# Sheet1.net
KiCad netlist of a schematic drawn in Altium Designer
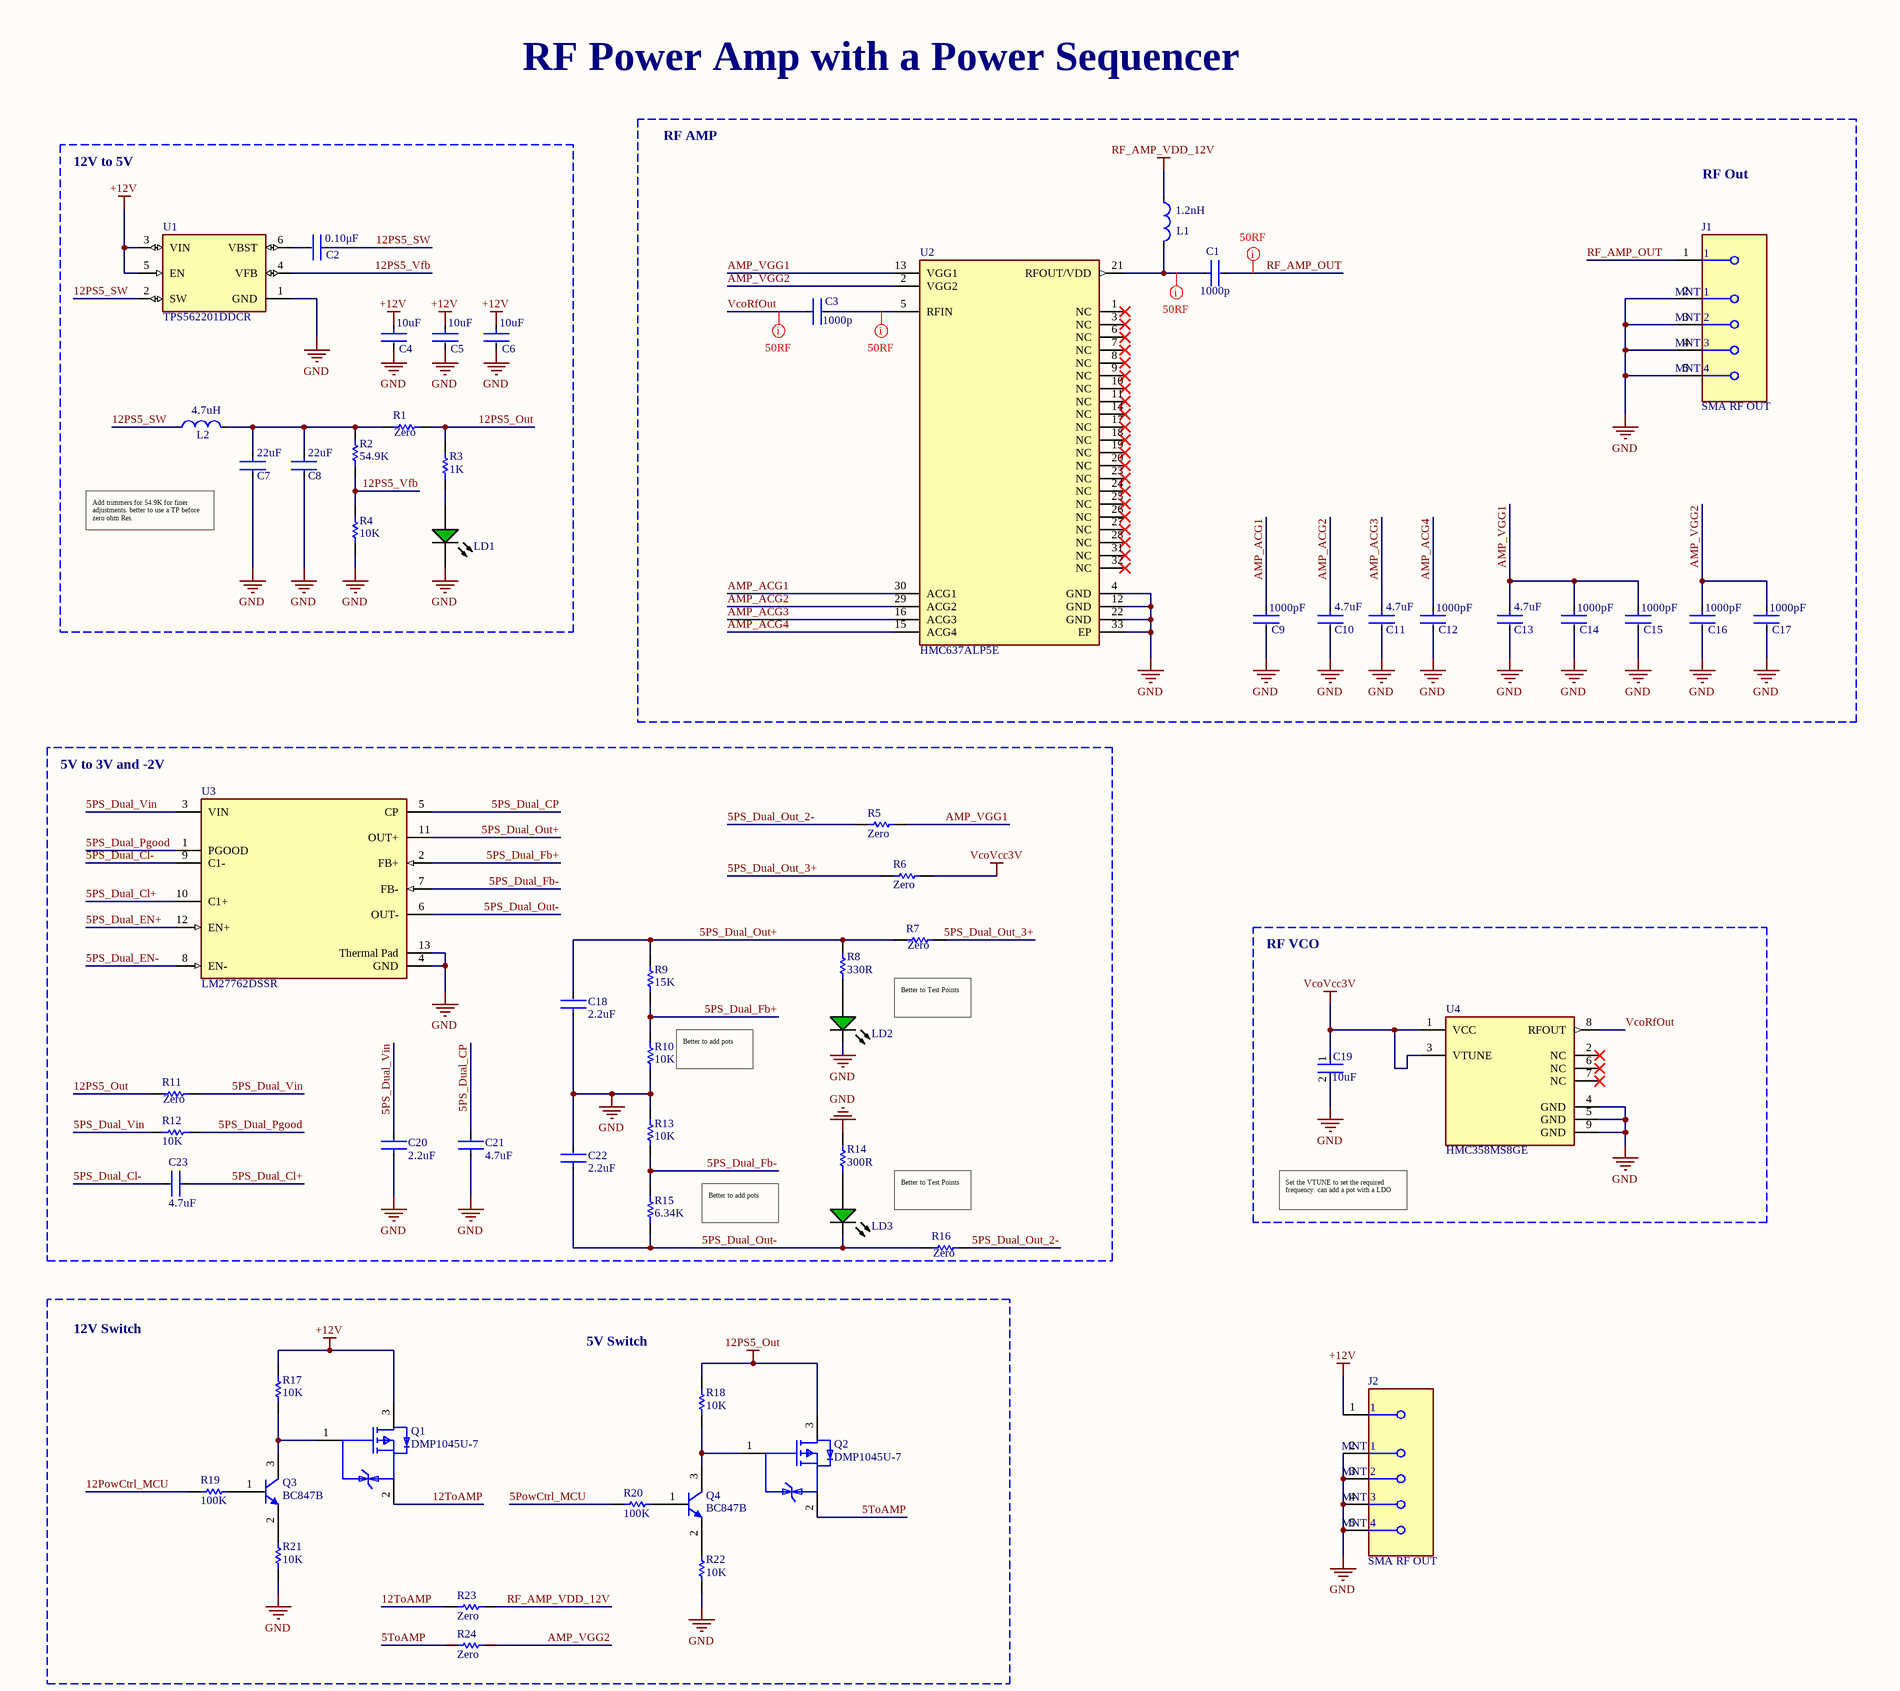
[diagram p0: Sheet1.SchDoc, top]
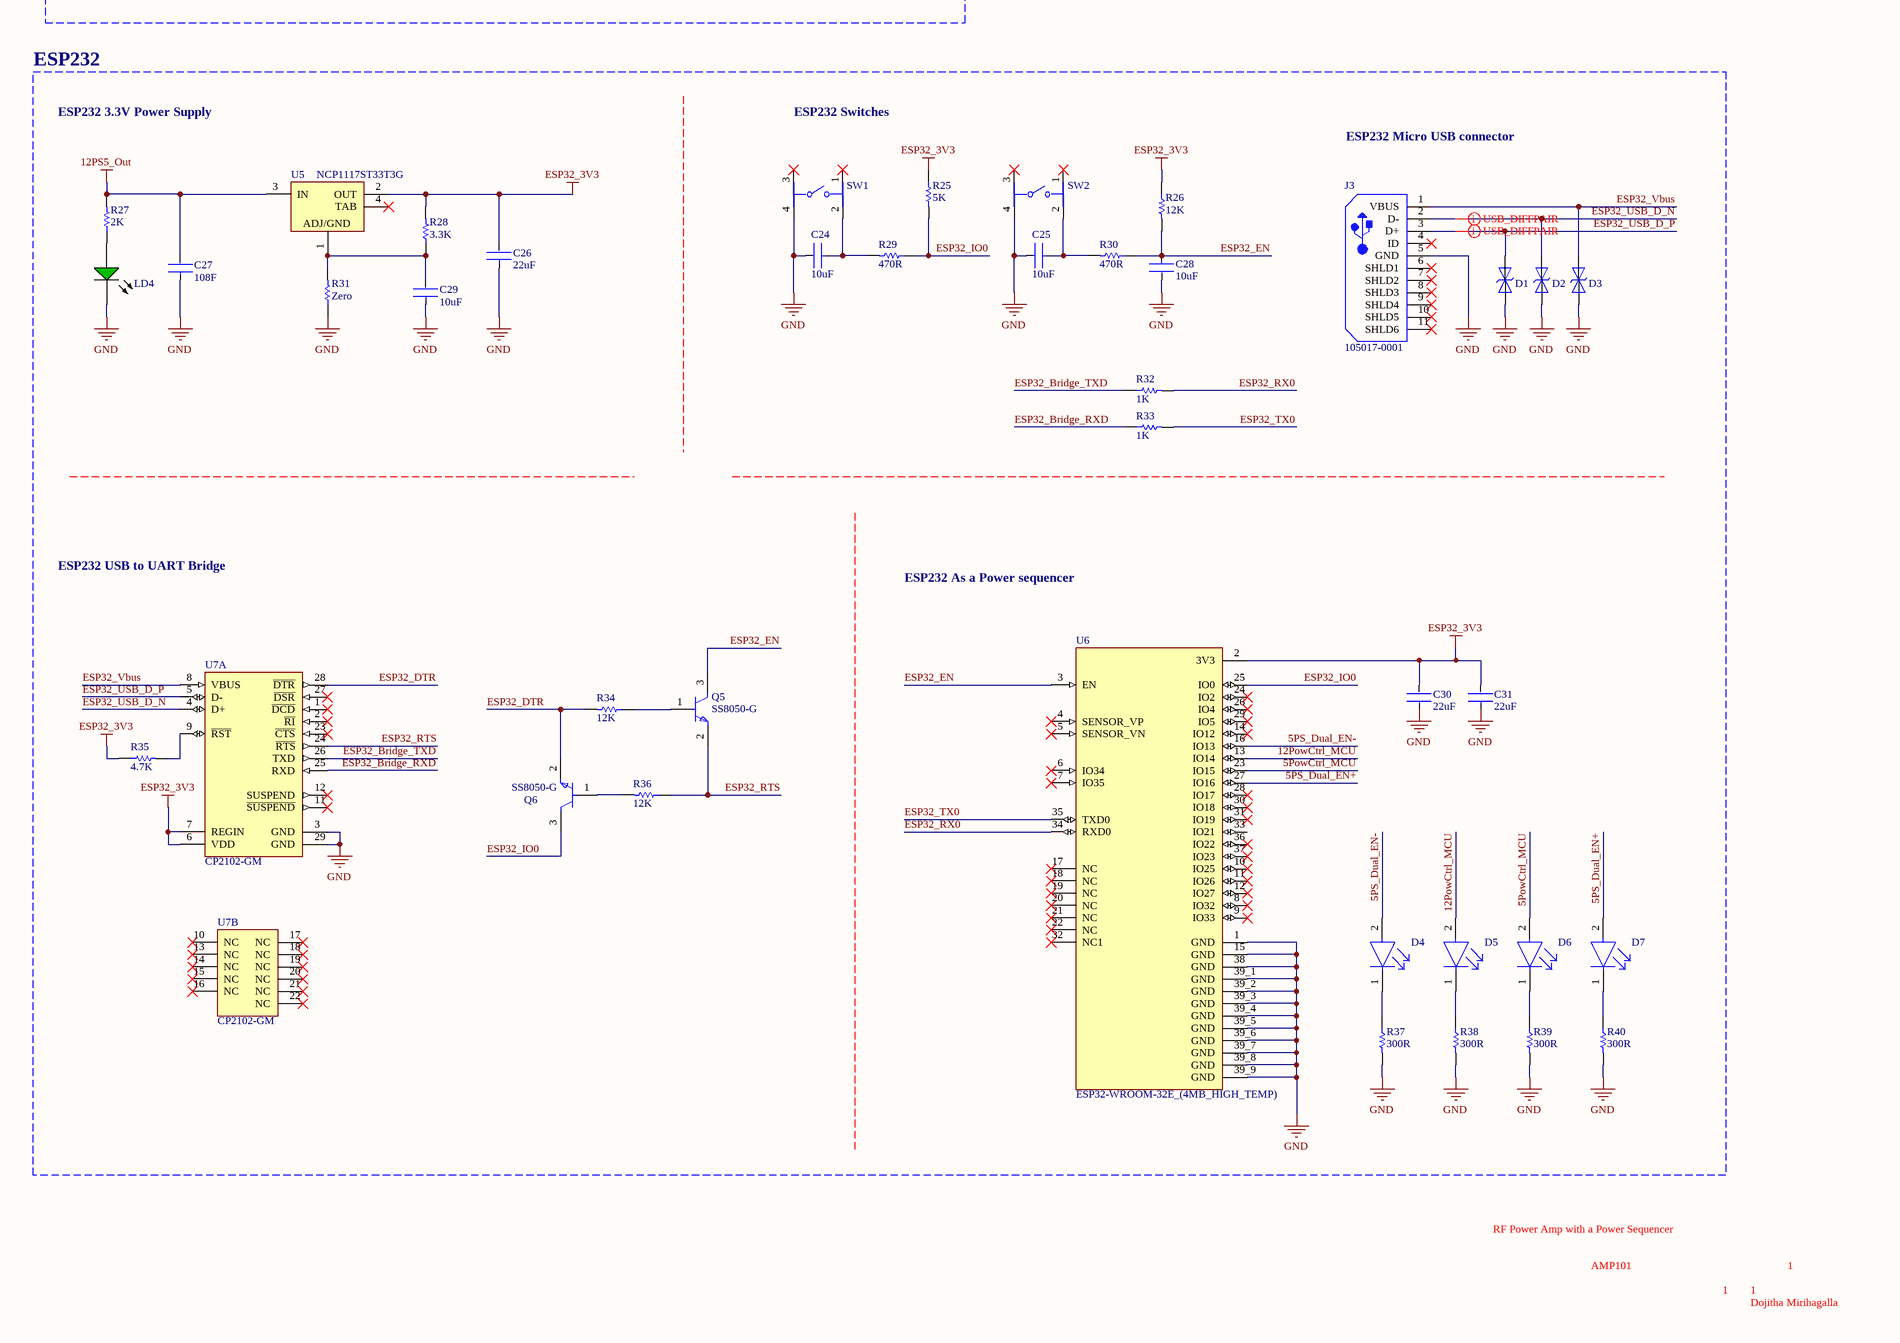
[diagram p1: Sheet1.SchDoc, bottom]

(export (version "E")
  (design (tool "Eeschema 10.0.6"))
  (components
    (comp (ref "C1")
      (value "GCM1555C1H102FA16D")
      (footprint "FP-GCM155-0_05-IPC_A")
      (description "Ceramic Capacitor for Automotive 1nF ±1% 50VDC C0G 0402 Paper T/R")
      (fields (field (name "CAPACITANCE") "1000p") (field (name "TOLERANCE") "1%"))
      (libsource (lib "Altium Content Vault") (part "02cd4be3c70576c341d710602a673aa"))
    )
    (comp (ref "C2")
      (value "GRM155R71C104KA88D")
      (footprint "FP-GRM15-MFG")
      (description "CAP CER 0.1UF 16V X7R 0402")
      (fields
        (field (name "TOLERANCE") "10%")
        (field (name "OCTOPART") "https://octopart.com/grm155r71c104ka88d-murata-196880")
        (field (name "CAPACITANCE") "0.10μF")
      )
      (libsource (lib "Altium Content Vault") (part "236180d848d6139a670b325ea6854c9"))
    )
    (comp (ref "C3")
      (value "GCM1555C1H102FA16D")
      (footprint "FP-GCM155-0_05-IPC_A")
      (description "Ceramic Capacitor for Automotive 1nF ±1% 50VDC C0G 0402 Paper T/R")
      (fields (field (name "CAPACITANCE") "1000p") (field (name "TOLERANCE") "1%"))
      (libsource (lib "Altium Content Vault") (part "02cd4be3c70576c341d710602a673aa"))
    )
    (comp (ref "C4")
      (value "GRM188R60J106ME47D")
      (footprint "FP-GRM188-0_1-e0_2_0_55-IPC_A")
      (description "Chip Multilayer Ceramic Capacitors for General Purpose, 0603, 10uF, X5R, 15%, 20%, 6.3V")
      (fields
        (field (name "CAPACITANCE") "10uF")
        (field (name "VOLTAGE") "6.3V")
        (field (name "TOLERANCE") "20%")
      )
      (libsource (lib "Altium Content Vault") (part "02cd4be3c70576c341d710602a673aa"))
    )
    (comp (ref "C5")
      (value "GRM188R60J106ME47D")
      (footprint "FP-GRM188-0_1-e0_2_0_55-IPC_A")
      (description "Chip Multilayer Ceramic Capacitors for General Purpose, 0603, 10uF, X5R, 15%, 20%, 6.3V")
      (fields
        (field (name "CAPACITANCE") "10uF")
        (field (name "VOLTAGE") "6.3V")
        (field (name "TOLERANCE") "20%")
      )
      (libsource (lib "Altium Content Vault") (part "02cd4be3c70576c341d710602a673aa"))
    )
    (comp (ref "C6")
      (value "GRM188R60J106ME47D")
      (footprint "FP-GRM188-0_1-e0_2_0_55-IPC_A")
      (description "Chip Multilayer Ceramic Capacitors for General Purpose, 0603, 10uF, X5R, 15%, 20%, 6.3V")
      (fields
        (field (name "CAPACITANCE") "10uF")
        (field (name "VOLTAGE") "6.3V")
        (field (name "TOLERANCE") "20%")
      )
      (libsource (lib "Altium Content Vault") (part "02cd4be3c70576c341d710602a673aa"))
    )
    (comp (ref "C7")
      (value "GRM21BR60J226ME39L")
      (footprint "FP-GRM21B-0_15-MFG")
      (description "Chip Multilayer Ceramic Capacitors for General Purpose, 0805, 22uF, X5R, 15%, 20%, 6.3V")
      (fields
        (field (name "VOLTAGE") "6.3V")
        (field (name "TOLERANCE") "20%")
        (field (name "CAPACITANCE") "22uF")
      )
      (libsource (lib "Altium Content Vault") (part "b4654b650e69147ec39a6b967a45e02"))
    )
    (comp (ref "C8")
      (value "GRM21BR60J226ME39L")
      (footprint "FP-GRM21B-0_15-MFG")
      (description "Chip Multilayer Ceramic Capacitors for General Purpose, 0805, 22uF, X5R, 15%, 20%, 6.3V")
      (fields
        (field (name "VOLTAGE") "6.3V")
        (field (name "TOLERANCE") "20%")
        (field (name "CAPACITANCE") "22uF")
      )
      (libsource (lib "Altium Content Vault") (part "b4654b650e69147ec39a6b967a45e02"))
    )
    (comp (ref "C9")
      (value "06035C102KAT2A")
      (footprint "FP-0603-L_1_6_0_15-W_0_81-IPC_A")
      (description "General Purpose Ceramic Capacitor, 0603, 1nF, 10%, X7R, 15%, 50V")
      (fields
        (field (name "CAPACITANCE") "1000pF")
        (field (name "VOLTAGE") "50V")
        (field (name "TOLERANCE") "10%")
      )
      (libsource (lib "Altium Content Vault") (part "02cd4be3c70576c341d710602a673aa"))
    )
    (comp (ref "C10")
      (value "CL05A475MP5NRNC")
      (footprint "FP-CL282-IPC_C")
      (description "Cap Ceramic 4.7uF 10V X5R ±20% SMD 0402 +85°C Paper T/R")
      (fields (field (name "CAPACITANCE") "4.7uF") (field (name "TOLERANCE") "20%"))
      (libsource (lib "Altium Content Vault") (part "b4654b650e69147ec39a6b967a45e02"))
    )
    (comp (ref "C11")
      (value "CL05A475MP5NRNC")
      (footprint "FP-CL282-IPC_C")
      (description "Cap Ceramic 4.7uF 10V X5R ±20% SMD 0402 +85°C Paper T/R")
      (fields (field (name "CAPACITANCE") "4.7uF") (field (name "TOLERANCE") "20%"))
      (libsource (lib "Altium Content Vault") (part "b4654b650e69147ec39a6b967a45e02"))
    )
    (comp (ref "C12")
      (value "06035C102KAT2A")
      (footprint "FP-0603-L_1_6_0_15-W_0_81-IPC_A")
      (description "General Purpose Ceramic Capacitor, 0603, 1nF, 10%, X7R, 15%, 50V")
      (fields
        (field (name "CAPACITANCE") "1000pF")
        (field (name "VOLTAGE") "50V")
        (field (name "TOLERANCE") "10%")
      )
      (libsource (lib "Altium Content Vault") (part "02cd4be3c70576c341d710602a673aa"))
    )
    (comp (ref "C13")
      (value "CL05A475MP5NRNC")
      (footprint "FP-CL282-IPC_C")
      (description "Cap Ceramic 4.7uF 10V X5R ±20% SMD 0402 +85°C Paper T/R")
      (fields (field (name "CAPACITANCE") "4.7uF") (field (name "TOLERANCE") "20%"))
      (libsource (lib "Altium Content Vault") (part "b4654b650e69147ec39a6b967a45e02"))
    )
    (comp (ref "C14")
      (value "06035C102KAT2A")
      (footprint "FP-0603-L_1_6_0_15-W_0_81-IPC_A")
      (description "General Purpose Ceramic Capacitor, 0603, 1nF, 10%, X7R, 15%, 50V")
      (fields
        (field (name "CAPACITANCE") "1000pF")
        (field (name "VOLTAGE") "50V")
        (field (name "TOLERANCE") "10%")
      )
      (libsource (lib "Altium Content Vault") (part "02cd4be3c70576c341d710602a673aa"))
    )
    (comp (ref "C15")
      (value "06035C102KAT2A")
      (footprint "FP-0603-L_1_6_0_15-W_0_81-IPC_A")
      (description "General Purpose Ceramic Capacitor, 0603, 1nF, 10%, X7R, 15%, 50V")
      (fields
        (field (name "CAPACITANCE") "1000pF")
        (field (name "VOLTAGE") "50V")
        (field (name "TOLERANCE") "10%")
      )
      (libsource (lib "Altium Content Vault") (part "02cd4be3c70576c341d710602a673aa"))
    )
    (comp (ref "C16")
      (value "06035C102KAT2A")
      (footprint "FP-0603-L_1_6_0_15-W_0_81-IPC_A")
      (description "General Purpose Ceramic Capacitor, 0603, 1nF, 10%, X7R, 15%, 50V")
      (fields
        (field (name "CAPACITANCE") "1000pF")
        (field (name "VOLTAGE") "50V")
        (field (name "TOLERANCE") "10%")
      )
      (libsource (lib "Altium Content Vault") (part "02cd4be3c70576c341d710602a673aa"))
    )
    (comp (ref "C17")
      (value "06035C102KAT2A")
      (footprint "FP-0603-L_1_6_0_15-W_0_81-IPC_A")
      (description "General Purpose Ceramic Capacitor, 0603, 1nF, 10%, X7R, 15%, 50V")
      (fields
        (field (name "CAPACITANCE") "1000pF")
        (field (name "VOLTAGE") "50V")
        (field (name "TOLERANCE") "10%")
      )
      (libsource (lib "Altium Content Vault") (part "02cd4be3c70576c341d710602a673aa"))
    )
    (comp (ref "C18")
      (value "CL05A475MP5NRNC")
      (footprint "FP-CL282-IPC_C")
      (description "Cap Ceramic 4.7uF 10V X5R ±20% SMD 0402 +85°C Paper T/R")
      (fields (field (name "CAPACITANCE") "2.2uF") (field (name "TOLERANCE") "20%"))
      (libsource (lib "Altium Content Vault") (part "b4654b650e69147ec39a6b967a45e02"))
    )
    (comp (ref "C19")
      (value "GRJ155R60J106ME11D")
      (footprint "FP-GRJ155-0_2-MFG")
      (description "CAP CER 10UF 6.3V X5R 0402")
      (fields (field (name "CAPACITANCE") "10uF") (field (name "TOLERANCE") "20%"))
      (libsource (lib "Altium Content Vault") (part "11868f565c42a9108669ba33697ecf6"))
    )
    (comp (ref "C20")
      (value "CL05A475MP5NRNC")
      (footprint "FP-CL282-IPC_C")
      (description "Cap Ceramic 4.7uF 10V X5R ±20% SMD 0402 +85°C Paper T/R")
      (fields (field (name "CAPACITANCE") "2.2uF") (field (name "TOLERANCE") "20%"))
      (libsource (lib "Altium Content Vault") (part "b4654b650e69147ec39a6b967a45e02"))
    )
    (comp (ref "C21")
      (value "CL05A475MP5NRNC")
      (footprint "FP-CL282-IPC_C")
      (description "Cap Ceramic 4.7uF 10V X5R ±20% SMD 0402 +85°C Paper T/R")
      (fields (field (name "CAPACITANCE") "4.7uF") (field (name "TOLERANCE") "20%"))
      (libsource (lib "Altium Content Vault") (part "b4654b650e69147ec39a6b967a45e02"))
    )
    (comp (ref "C22")
      (value "CL05A475MP5NRNC")
      (footprint "FP-CL282-IPC_C")
      (description "Cap Ceramic 4.7uF 10V X5R ±20% SMD 0402 +85°C Paper T/R")
      (fields (field (name "CAPACITANCE") "2.2uF") (field (name "TOLERANCE") "20%"))
      (libsource (lib "Altium Content Vault") (part "b4654b650e69147ec39a6b967a45e02"))
    )
    (comp (ref "C23")
      (value "CL05A475MP5NRNC")
      (footprint "FP-CL282-IPC_C")
      (description "Cap Ceramic 4.7uF 10V X5R ±20% SMD 0402 +85°C Paper T/R")
      (fields (field (name "CAPACITANCE") "4.7uF") (field (name "TOLERANCE") "20%"))
      (libsource (lib "Altium Content Vault") (part "b4654b650e69147ec39a6b967a45e02"))
    )
    (comp (ref "C24")
      (value "CL05A475MP5NRNC")
      (footprint "FP-CL282-IPC_C")
      (description "Cap Ceramic 4.7uF 10V X5R ±20% SMD 0402 +85°C Paper T/R")
      (fields (field (name "CAPACITANCE") "10uF") (field (name "TOLERANCE") "20%"))
      (libsource (lib "Altium Content Vault") (part "b4654b650e69147ec39a6b967a45e02"))
    )
    (comp (ref "C25")
      (value "CL05A475MP5NRNC")
      (footprint "FP-CL282-IPC_C")
      (description "Cap Ceramic 4.7uF 10V X5R ±20% SMD 0402 +85°C Paper T/R")
      (fields (field (name "CAPACITANCE") "10uF") (field (name "TOLERANCE") "20%"))
      (libsource (lib "Altium Content Vault") (part "b4654b650e69147ec39a6b967a45e02"))
    )
    (comp (ref "C26")
      (value "CL05A475MP5NRNC")
      (footprint "FP-CL282-IPC_C")
      (description "Cap Ceramic 4.7uF 10V X5R ±20% SMD 0402 +85°C Paper T/R")
      (fields (field (name "CAPACITANCE") "22uF") (field (name "TOLERANCE") "20%"))
      (libsource (lib "Altium Content Vault") (part "b4654b650e69147ec39a6b967a45e02"))
    )
    (comp (ref "C27")
      (value "CL05A475MP5NRNC")
      (footprint "FP-CL282-IPC_C")
      (description "Cap Ceramic 4.7uF 10V X5R ±20% SMD 0402 +85°C Paper T/R")
      (fields (field (name "CAPACITANCE") "108F") (field (name "TOLERANCE") "20%"))
      (libsource (lib "Altium Content Vault") (part "b4654b650e69147ec39a6b967a45e02"))
    )
    (comp (ref "C28")
      (value "CL05A475MP5NRNC")
      (footprint "FP-CL282-IPC_C")
      (description "Cap Ceramic 4.7uF 10V X5R ±20% SMD 0402 +85°C Paper T/R")
      (fields (field (name "CAPACITANCE") "10uF") (field (name "TOLERANCE") "20%"))
      (libsource (lib "Altium Content Vault") (part "b4654b650e69147ec39a6b967a45e02"))
    )
    (comp (ref "C29")
      (value "CL05A475MP5NRNC")
      (footprint "FP-CL282-IPC_C")
      (description "Cap Ceramic 4.7uF 10V X5R ±20% SMD 0402 +85°C Paper T/R")
      (fields (field (name "CAPACITANCE") "10uF") (field (name "TOLERANCE") "20%"))
      (libsource (lib "Altium Content Vault") (part "b4654b650e69147ec39a6b967a45e02"))
    )
    (comp (ref "C30")
      (value "CL05A475MP5NRNC")
      (footprint "FP-CL282-IPC_C")
      (description "Cap Ceramic 4.7uF 10V X5R ±20% SMD 0402 +85°C Paper T/R")
      (fields (field (name "CAPACITANCE") "22uF") (field (name "TOLERANCE") "20%"))
      (libsource (lib "Altium Content Vault") (part "b4654b650e69147ec39a6b967a45e02"))
    )
    (comp (ref "C31")
      (value "CL05A475MP5NRNC")
      (footprint "FP-CL282-IPC_C")
      (description "Cap Ceramic 4.7uF 10V X5R ±20% SMD 0402 +85°C Paper T/R")
      (fields (field (name "CAPACITANCE") "22uF") (field (name "TOLERANCE") "20%"))
      (libsource (lib "Altium Content Vault") (part "b4654b650e69147ec39a6b967a45e02"))
    )
    (comp (ref "D1")
      (value "SMF16A")
      (footprint "SODFL3718X102N")
      (description "200W, 18.8V, 5%, Unidirectional, TVS")
      (fields (field (name "MF") "Taiwan Semiconductor"))
      (libsource (lib "Schlib1") (part "SMF16A"))
    )
    (comp (ref "D2")
      (value "SMF16A")
      (footprint "SODFL3718X102N")
      (description "200W, 18.8V, 5%, Unidirectional, TVS")
      (fields (field (name "MF") "Taiwan Semiconductor"))
      (libsource (lib "Schlib1") (part "SMF16A"))
    )
    (comp (ref "D3")
      (value "SMF16A")
      (footprint "SODFL3718X102N")
      (description "200W, 18.8V, 5%, Unidirectional, TVS")
      (fields (field (name "MF") "Taiwan Semiconductor"))
      (libsource (lib "Schlib1") (part "SMF16A"))
    )
    (comp (ref "D4")
      (value "LTST-C191TBKT")
      (footprint "FP-LTST-C191TBKT-MFG")
      (description "LED BLUE CLEAR CHIP SMD")
      (libsource (lib "Altium Content Vault") (part "8706943c75ba83719d021d2fdc84c58"))
    )
    (comp (ref "D5")
      (value "LTST-C191TBKT")
      (footprint "FP-LTST-C191TBKT-MFG")
      (description "LED BLUE CLEAR CHIP SMD")
      (libsource (lib "Altium Content Vault") (part "8706943c75ba83719d021d2fdc84c58"))
    )
    (comp (ref "D6")
      (value "LTST-C191TBKT")
      (footprint "FP-LTST-C191TBKT-MFG")
      (description "LED BLUE CLEAR CHIP SMD")
      (libsource (lib "Altium Content Vault") (part "8706943c75ba83719d021d2fdc84c58"))
    )
    (comp (ref "D7")
      (value "LTST-C191TBKT")
      (footprint "FP-LTST-C191TBKT-MFG")
      (description "LED BLUE CLEAR CHIP SMD")
      (libsource (lib "Altium Content Vault") (part "8706943c75ba83719d021d2fdc84c58"))
    )
    (comp (ref "J1")
      (value "SMA RF OUT")
      (footprint "FP-SMA-J-P-H-ST-EM1-MFG")
      (description "CONN SMA JACK STR 50OHM EDGE MNT")
      (libsource (lib "Altium Content Vault") (part "c65b8a639cdaef1819ea20b5466f8fa"))
    )
    (comp (ref "J2")
      (value "SMA RF OUT")
      (footprint "FP-SMA-J-P-H-ST-EM1-MFG")
      (description "CONN SMA JACK STR 50OHM EDGE MNT")
      (libsource (lib "Altium Content Vault") (part "c65b8a639cdaef1819ea20b5466f8fa"))
    )
    (comp (ref "J3")
      (value "105017-0001")
      (footprint "USB-MICRO-B_V")
      (fields (field (name "MANUFACTURER") "Molex"))
      (libsource (lib "Altium Content Vault") (part "USB-5-6SHLD"))
    )
    (comp (ref "L1")
      (value "LQP03HQ1N2B02D")
      (footprint "FP-LQP03HQ_02-MFG")
      (description "Film type RF Inductor 1.2nH ±0.1nH 1100mA 0.04Ω 0201 (0603)")
      (fields (field (name "INDUCTANCE") "1.2nH"))
      (libsource (lib "Altium Content Vault") (part "725321dda6339637d4d059423bc1c3c"))
    )
    (comp (ref "L2")
      (value "NR6028T4R7M")
      (footprint "FP-NR6028-MFG")
      (description "SMD Power Inductors 4.7uH ±20% 2.7A 40.3mΩ")
      (fields (field (name "INDUCTANCE") "4.7uH") (field (name "TOLERANCE") "20%"))
      (libsource (lib "Altium Content Vault") (part "725321dda6339637d4d059423bc1c3c"))
    )
    (comp (ref "LD1")
      (value "HSMG-C170")
      (footprint "AVAG-HSMX-C170_V")
      (description "Chip LED, Green, 2.2 V, -40 to 85 degC, 2-Pin SMD, Pb-Free, Tape and Reel")
      (fields (field (name "MANUFACTURER") "Avago"))
      (libsource (lib "Altium Content Vault") (part "LED_GREEN_A1K2-2"))
    )
    (comp (ref "LD2")
      (value "HSMG-C170")
      (footprint "AVAG-HSMX-C170_V")
      (description "Chip LED, Green, 2.2 V, -40 to 85 degC, 2-Pin SMD, Pb-Free, Tape and Reel")
      (fields (field (name "MANUFACTURER") "Avago"))
      (libsource (lib "Altium Content Vault") (part "LED_GREEN_A1K2-2"))
    )
    (comp (ref "LD3")
      (value "HSMG-C170")
      (footprint "AVAG-HSMX-C170_V")
      (description "Chip LED, Green, 2.2 V, -40 to 85 degC, 2-Pin SMD, Pb-Free, Tape and Reel")
      (fields (field (name "MANUFACTURER") "Avago"))
      (libsource (lib "Altium Content Vault") (part "LED_GREEN_A1K2-2"))
    )
    (comp (ref "LD4")
      (value "HSMG-C170")
      (footprint "AVAG-HSMX-C170_V")
      (description "Chip LED, Green, 2.2 V, -40 to 85 degC, 2-Pin SMD, Pb-Free, Tape and Reel")
      (fields (field (name "MANUFACTURER") "Avago"))
      (libsource (lib "Altium Content Vault") (part "LED_GREEN_A1K2-2"))
    )
    (comp (ref "Q1")
      (value "DMP1045U-7")
      (footprint "FP-SOT23-MFG")
      (description "MOSFET P-CH 12V 4A SOT23")
      (fields
        (field (name "MANUFACTURER") "Diodes Inc.")
        (field (name "OCTOPART") "https://octopart.com/dmp1045u-7-diodes+inc.-20474459")
      )
      (libsource (lib "Altium Content Vault") (part "16f57cea3a39b7f0ecfb5a0737525d1"))
    )
    (comp (ref "Q2")
      (value "DMP1045U-7")
      (footprint "FP-SOT23-MFG")
      (description "MOSFET P-CH 12V 4A SOT23")
      (fields
        (field (name "MANUFACTURER") "Diodes Inc.")
        (field (name "OCTOPART") "https://octopart.com/dmp1045u-7-diodes+inc.-20474459")
      )
      (libsource (lib "Altium Content Vault") (part "16f57cea3a39b7f0ecfb5a0737525d1"))
    )
    (comp (ref "Q3")
      (value "BC847B")
      (footprint "INF-SOT23_M")
      (description "NPN Silicon AF Transistor, 45 V VCEO, 100 mA IC, SOT23, Reel, Green")
      (fields (field (name "MANUFACTURER") "Infineon"))
      (libsource (lib "Altium Content Vault") (part "INF-BJTNPN-BEC-3"))
    )
    (comp (ref "Q4")
      (value "BC847B")
      (footprint "INF-SOT23_M")
      (description "NPN Silicon AF Transistor, 45 V VCEO, 100 mA IC, SOT23, Reel, Green")
      (fields (field (name "MANUFACTURER") "Infineon"))
      (libsource (lib "Altium Content Vault") (part "INF-BJTNPN-BEC-3"))
    )
    (comp (ref "Q5")
      (value "SS8050-G")
      (footprint "FP-SS8050-G-MFG")
      (description "NPN TRANSISTOR 1.5A 40V SOT-23 R")
      (libsource (lib "Altium Content Vault") (part "2a1388f82443b098dcd57d24ac7632d"))
    )
    (comp (ref "Q6")
      (value "SS8050-G")
      (footprint "FP-SS8050-G-MFG")
      (description "NPN TRANSISTOR 1.5A 40V SOT-23 R")
      (libsource (lib "Altium Content Vault") (part "2a1388f82443b098dcd57d24ac7632d"))
    )
    (comp (ref "R1")
      (value "CRCW060354K9FKEA")
      (footprint "RESC1609X50X30LL10T20")
      (fields (field (name "MANUFACTURER") "Vishay Dale") (field (name "RESISTANCE") "Zero"))
      (libsource (lib "Altium Content Vault") (part "RES"))
    )
    (comp (ref "R2")
      (value "CRCW060354K9FKEA")
      (footprint "RESC1609X50X30LL10T20")
      (fields (field (name "MANUFACTURER") "Vishay Dale") (field (name "RESISTANCE") "54.9K"))
      (libsource (lib "Altium Content Vault") (part "RES"))
    )
    (comp (ref "R3")
      (value "CRCW060354K9FKEA")
      (footprint "RESC1609X50X30LL10T20")
      (fields (field (name "MANUFACTURER") "Vishay Dale") (field (name "RESISTANCE") "1K"))
      (libsource (lib "Altium Content Vault") (part "RES"))
    )
    (comp (ref "R4")
      (value "CRCW060354K9FKEA")
      (footprint "RESC1609X50X30LL10T20")
      (fields (field (name "MANUFACTURER") "Vishay Dale") (field (name "RESISTANCE") "10K"))
      (libsource (lib "Altium Content Vault") (part "RES"))
    )
    (comp (ref "R5")
      (value "CRCW060354K9FKEA")
      (footprint "RESC1609X50X30LL10T20")
      (fields (field (name "MANUFACTURER") "Vishay Dale") (field (name "RESISTANCE") "Zero"))
      (libsource (lib "Altium Content Vault") (part "RES"))
    )
    (comp (ref "R6")
      (value "CRCW060354K9FKEA")
      (footprint "RESC1609X50X30LL10T20")
      (fields (field (name "MANUFACTURER") "Vishay Dale") (field (name "RESISTANCE") "Zero"))
      (libsource (lib "Altium Content Vault") (part "RES"))
    )
    (comp (ref "R7")
      (value "CRCW060354K9FKEA")
      (footprint "RESC1609X50X30LL10T20")
      (fields (field (name "MANUFACTURER") "Vishay Dale") (field (name "RESISTANCE") "Zero"))
      (libsource (lib "Altium Content Vault") (part "RES"))
    )
    (comp (ref "R8")
      (value "CRCW060354K9FKEA")
      (footprint "RESC1609X50X30LL10T20")
      (fields (field (name "MANUFACTURER") "Vishay Dale") (field (name "RESISTANCE") "330R"))
      (libsource (lib "Altium Content Vault") (part "RES"))
    )
    (comp (ref "R9")
      (value "CRCW060354K9FKEA")
      (footprint "RESC1609X50X30LL10T20")
      (fields (field (name "MANUFACTURER") "Vishay Dale") (field (name "RESISTANCE") "15K"))
      (libsource (lib "Altium Content Vault") (part "RES"))
    )
    (comp (ref "R10")
      (value "CRCW060354K9FKEA")
      (footprint "RESC1609X50X30LL10T20")
      (fields (field (name "MANUFACTURER") "Vishay Dale") (field (name "RESISTANCE") "10K"))
      (libsource (lib "Altium Content Vault") (part "RES"))
    )
    (comp (ref "R11")
      (value "CRCW060354K9FKEA")
      (footprint "RESC1609X50X30LL10T20")
      (fields (field (name "MANUFACTURER") "Vishay Dale") (field (name "RESISTANCE") "Zero"))
      (libsource (lib "Altium Content Vault") (part "RES"))
    )
    (comp (ref "R12")
      (value "CRCW060354K9FKEA")
      (footprint "RESC1609X50X30LL10T20")
      (fields (field (name "MANUFACTURER") "Vishay Dale") (field (name "RESISTANCE") "10K"))
      (libsource (lib "Altium Content Vault") (part "RES"))
    )
    (comp (ref "R13")
      (value "CRCW060354K9FKEA")
      (footprint "RESC1609X50X30LL10T20")
      (fields (field (name "MANUFACTURER") "Vishay Dale") (field (name "RESISTANCE") "10K"))
      (libsource (lib "Altium Content Vault") (part "RES"))
    )
    (comp (ref "R14")
      (value "CRCW060354K9FKEA")
      (footprint "RESC1609X50X30LL10T20")
      (fields (field (name "MANUFACTURER") "Vishay Dale") (field (name "RESISTANCE") "300R"))
      (libsource (lib "Altium Content Vault") (part "RES"))
    )
    (comp (ref "R15")
      (value "CRCW060354K9FKEA")
      (footprint "RESC1609X50X30LL10T20")
      (fields (field (name "MANUFACTURER") "Vishay Dale") (field (name "RESISTANCE") "6.34K"))
      (libsource (lib "Altium Content Vault") (part "RES"))
    )
    (comp (ref "R16")
      (value "CRCW060354K9FKEA")
      (footprint "RESC1609X50X30LL10T20")
      (fields (field (name "MANUFACTURER") "Vishay Dale") (field (name "RESISTANCE") "Zero"))
      (libsource (lib "Altium Content Vault") (part "RES"))
    )
    (comp (ref "R17")
      (value "CRCW060354K9FKEA")
      (footprint "RESC1609X50X30LL10T20")
      (fields (field (name "MANUFACTURER") "Vishay Dale") (field (name "RESISTANCE") "10K"))
      (libsource (lib "Altium Content Vault") (part "RES"))
    )
    (comp (ref "R18")
      (value "CRCW060354K9FKEA")
      (footprint "RESC1609X50X30LL10T20")
      (fields (field (name "MANUFACTURER") "Vishay Dale") (field (name "RESISTANCE") "10K"))
      (libsource (lib "Altium Content Vault") (part "RES"))
    )
    (comp (ref "R19")
      (value "CRCW060354K9FKEA")
      (footprint "RESC1609X50X30LL10T20")
      (fields (field (name "MANUFACTURER") "Vishay Dale") (field (name "RESISTANCE") "100K"))
      (libsource (lib "Altium Content Vault") (part "RES"))
    )
    (comp (ref "R20")
      (value "CRCW060354K9FKEA")
      (footprint "RESC1609X50X30LL10T20")
      (fields (field (name "MANUFACTURER") "Vishay Dale") (field (name "RESISTANCE") "100K"))
      (libsource (lib "Altium Content Vault") (part "RES"))
    )
    (comp (ref "R21")
      (value "CRCW060354K9FKEA")
      (footprint "RESC1609X50X30LL10T20")
      (fields (field (name "MANUFACTURER") "Vishay Dale") (field (name "RESISTANCE") "10K"))
      (libsource (lib "Altium Content Vault") (part "RES"))
    )
    (comp (ref "R22")
      (value "CRCW060354K9FKEA")
      (footprint "RESC1609X50X30LL10T20")
      (fields (field (name "MANUFACTURER") "Vishay Dale") (field (name "RESISTANCE") "10K"))
      (libsource (lib "Altium Content Vault") (part "RES"))
    )
    (comp (ref "R23")
      (value "CRCW060354K9FKEA")
      (footprint "RESC1609X50X30LL10T20")
      (fields (field (name "MANUFACTURER") "Vishay Dale") (field (name "RESISTANCE") "Zero"))
      (libsource (lib "Altium Content Vault") (part "RES"))
    )
    (comp (ref "R24")
      (value "CRCW060354K9FKEA")
      (footprint "RESC1609X50X30LL10T20")
      (fields (field (name "MANUFACTURER") "Vishay Dale") (field (name "RESISTANCE") "Zero"))
      (libsource (lib "Altium Content Vault") (part "RES"))
    )
    (comp (ref "R25")
      (value "CRCW060354K9FKEA")
      (footprint "RESC1609X50X30LL10T20")
      (fields (field (name "MANUFACTURER") "Vishay Dale") (field (name "RESISTANCE") "5K"))
      (libsource (lib "Altium Content Vault") (part "RES"))
    )
    (comp (ref "R26")
      (value "CRCW060354K9FKEA")
      (footprint "RESC1609X50X30LL10T20")
      (fields (field (name "MANUFACTURER") "Vishay Dale") (field (name "RESISTANCE") "12K"))
      (libsource (lib "Altium Content Vault") (part "RES"))
    )
    (comp (ref "R27")
      (value "CRCW060354K9FKEA")
      (footprint "RESC1609X50X30LL10T20")
      (fields (field (name "MANUFACTURER") "Vishay Dale") (field (name "RESISTANCE") "2K"))
      (libsource (lib "Altium Content Vault") (part "RES"))
    )
    (comp (ref "R28")
      (value "CRCW060354K9FKEA")
      (footprint "RESC1609X50X30LL10T20")
      (fields (field (name "MANUFACTURER") "Vishay Dale") (field (name "RESISTANCE") "3.3K"))
      (libsource (lib "Altium Content Vault") (part "RES"))
    )
    (comp (ref "R29")
      (value "CRCW060354K9FKEA")
      (footprint "RESC1609X50X30LL10T20")
      (fields (field (name "MANUFACTURER") "Vishay Dale") (field (name "RESISTANCE") "470R"))
      (libsource (lib "Altium Content Vault") (part "RES"))
    )
    (comp (ref "R30")
      (value "CRCW060354K9FKEA")
      (footprint "RESC1609X50X30LL10T20")
      (fields (field (name "MANUFACTURER") "Vishay Dale") (field (name "RESISTANCE") "470R"))
      (libsource (lib "Altium Content Vault") (part "RES"))
    )
    (comp (ref "R31")
      (value "CRCW060354K9FKEA")
      (footprint "RESC1609X50X30LL10T20")
      (fields (field (name "MANUFACTURER") "Vishay Dale") (field (name "RESISTANCE") "Zero"))
      (libsource (lib "Altium Content Vault") (part "RES"))
    )
    (comp (ref "R32")
      (value "CRCW060354K9FKEA")
      (footprint "RESC1609X50X30LL10T20")
      (fields (field (name "MANUFACTURER") "Vishay Dale") (field (name "RESISTANCE") "1K"))
      (libsource (lib "Altium Content Vault") (part "RES"))
    )
    (comp (ref "R33")
      (value "CRCW060354K9FKEA")
      (footprint "RESC1609X50X30LL10T20")
      (fields (field (name "MANUFACTURER") "Vishay Dale") (field (name "RESISTANCE") "1K"))
      (libsource (lib "Altium Content Vault") (part "RES"))
    )
    (comp (ref "R34")
      (value "CRCW060354K9FKEA")
      (footprint "RESC1609X50X30LL10T20")
      (fields (field (name "MANUFACTURER") "Vishay Dale") (field (name "RESISTANCE") "12K"))
      (libsource (lib "Altium Content Vault") (part "RES"))
    )
    (comp (ref "R35")
      (value "CRCW060354K9FKEA")
      (footprint "RESC1609X50X30LL10T20")
      (fields (field (name "MANUFACTURER") "Vishay Dale") (field (name "RESISTANCE") "4.7K"))
      (libsource (lib "Altium Content Vault") (part "RES"))
    )
    (comp (ref "R36")
      (value "CRCW060354K9FKEA")
      (footprint "RESC1609X50X30LL10T20")
      (fields (field (name "MANUFACTURER") "Vishay Dale") (field (name "RESISTANCE") "12K"))
      (libsource (lib "Altium Content Vault") (part "RES"))
    )
    (comp (ref "R37")
      (value "CRCW060354K9FKEA")
      (footprint "RESC1609X50X30LL10T20")
      (fields (field (name "MANUFACTURER") "Vishay Dale") (field (name "RESISTANCE") "300R"))
      (libsource (lib "Altium Content Vault") (part "RES"))
    )
    (comp (ref "R38")
      (value "CRCW060354K9FKEA")
      (footprint "RESC1609X50X30LL10T20")
      (fields (field (name "MANUFACTURER") "Vishay Dale") (field (name "RESISTANCE") "300R"))
      (libsource (lib "Altium Content Vault") (part "RES"))
    )
    (comp (ref "R39")
      (value "CRCW060354K9FKEA")
      (footprint "RESC1609X50X30LL10T20")
      (fields (field (name "MANUFACTURER") "Vishay Dale") (field (name "RESISTANCE") "300R"))
      (libsource (lib "Altium Content Vault") (part "RES"))
    )
    (comp (ref "R40")
      (value "CRCW060354K9FKEA")
      (footprint "RESC1609X50X30LL10T20")
      (fields (field (name "MANUFACTURER") "Vishay Dale") (field (name "RESISTANCE") "300R"))
      (libsource (lib "Altium Content Vault") (part "RES"))
    )
    (comp (ref "SW1")
      (value "PTS645SM43SMTR92LFS")
      (footprint "FP-PTS645SM43SMTR92LFS-MFG")
      (description "SWITCH TACTILE SPST-NO 0.05A 12V")
      (libsource (lib "Altium Content Vault") (part "1adf0dd01260c80cf25a44bfd6b99ba"))
    )
    (comp (ref "SW2")
      (value "PTS645SM43SMTR92LFS")
      (footprint "FP-PTS645SM43SMTR92LFS-MFG")
      (description "SWITCH TACTILE SPST-NO 0.05A 12V")
      (libsource (lib "Altium Content Vault") (part "1adf0dd01260c80cf25a44bfd6b99ba"))
    )
    (comp (ref "U1")
      (value "TPS562201DDCR")
      (footprint "FP-DDC0006A-IPC_C")
      (description "IC REG BUCK ADJ 2A TSOT23-6")
      (libsource (lib "Altium Content Vault") (part "957e164956730ea4bf6293280af19fc"))
    )
    (comp (ref "U2")
      (value "HMC637ALP5E")
      (footprint "FP-HCP-32-1-IPC_A")
      (description "IC MMIC MESFET GAAS 1W 32-QFN")
      (libsource (lib "Schlib1") (part "CMP-09142-000117-1"))
    )
    (comp (ref "U3")
      (value "LM27762DSSR")
      (footprint "FP-DSS0012B-MFG")
      (description "IC REG CHARGE PUMP ADJ DL 12WSON")
      (libsource (lib "Altium Content Vault") (part "ab275a4f98ccada617dcf409ec46a20"))
    )
    (comp (ref "U4")
      (value "HMC358MS8GE")
      (footprint "FP-MS8GE-MFG")
      (description "IC MMIC AMP VCO BUFFER 8-MSOP")
      (libsource (lib "Schlib1") (part "CMP-09141-000299-1"))
    )
    (comp (ref "U5")
      (value "NCP1117ST33T3G")
      (footprint "ONSC-SOT-223-4-318H-01_A_V")
      (fields (field (name "TOLERANCE") "1%"))
      (libsource (lib "Altium Content Vault") (part "ONSC-NCP1117-SOT223-4"))
    )
    (comp (ref "U6")
      (value "ESP32-WROOM-32E_(4MB_HIGH_TEMP)")
      (footprint "XCVR_ESP32-WROOM-32E_(4MB_HIGH_TEMP)")
      (fields (field (name "MF") "Espressif Systems") (field (name "MP") "ESP32-WROOM-32E (4MB HIGH TEMP)"))
      (libsource (lib "Schlib1") (part "ESP32-WROOM-32E_(4MB_HIGH_TEMP)"))
    )
    (comp (ref "U7")
      (value "CP2102-GM")
      (footprint "SLAB-QFN-28-3125x3125TP_N")
      (description "Single-Chip USB to UART Bridge, 1024 Bytes EEPROM, -40 to 85 degC, 28-pin QFN, Tube")
      (fields (field (name "MANUFACTURER") "Silicon Labs"))
      (libsource (lib "Altium Content Vault") (part "SLAB-CP210X-QFN-28-29"))
    )
  )
  (nets
    (net (code "1") (name "+12V") (class "Default")
      (node (ref "C4") (pin "1") (pinfunction "1_1") (pintype "passive"))
      (node (ref "C5") (pin "1") (pinfunction "1_1") (pintype "passive"))
      (node (ref "C6") (pin "1") (pinfunction "1_1") (pintype "passive"))
      (node (ref "J2") (pin "1") (pinfunction "1_1") (pintype "passive"))
      (node (ref "Q1") (pin "3") (pinfunction "D_3") (pintype "passive"))
      (node (ref "R17") (pin "2") (pinfunction "2_2") (pintype "passive"))
      (node (ref "U1") (pin "3") (pinfunction "VIN_3") (pintype "bidirectional"))
      (node (ref "U1") (pin "5") (pinfunction "EN_5") (pintype "input"))
    )
    (net (code "2") (name "/5PS_Dual_CP") (class "Default")
      (node (ref "C21") (pin "2") (pinfunction "2_2") (pintype "passive"))
      (node (ref "U3") (pin "5") (pinfunction "CP_5") (pintype "passive"))
    )
    (net (code "3") (name "/5PS_Dual_Cl+") (class "Default")
      (node (ref "C23") (pin "1") (pinfunction "1_1") (pintype "passive"))
      (node (ref "U3") (pin "10") (pinfunction "C1+_10") (pintype "passive"))
    )
    (net (code "4") (name "/5PS_Dual_Cl-") (class "Default")
      (node (ref "C23") (pin "2") (pinfunction "2_2") (pintype "passive"))
      (node (ref "U3") (pin "9") (pinfunction "C1-_9") (pintype "passive"))
    )
    (net (code "5") (name "/5PS_Dual_EN+") (class "Default")
      (node (ref "D7") (pin "2") (pinfunction "A_2") (pintype "passive"))
      (node (ref "U3") (pin "12") (pinfunction "EN+_12") (pintype "input"))
      (node (ref "U6") (pin "27") (pinfunction "IO16_27") (pintype "bidirectional"))
    )
    (net (code "6") (name "/5PS_Dual_EN-") (class "Default")
      (node (ref "D4") (pin "2") (pinfunction "A_2") (pintype "passive"))
      (node (ref "U3") (pin "8") (pinfunction "EN-_8") (pintype "input"))
      (node (ref "U6") (pin "16") (pinfunction "IO13_16") (pintype "bidirectional"))
    )
    (net (code "7") (name "/5PS_Dual_Fb+") (class "Default")
      (node (ref "R10") (pin "2") (pinfunction "2_2") (pintype "passive"))
      (node (ref "R9") (pin "1") (pinfunction "1_1") (pintype "passive"))
      (node (ref "U3") (pin "2") (pinfunction "FB+_2") (pintype "input"))
    )
    (net (code "8") (name "/5PS_Dual_Fb-") (class "Default")
      (node (ref "R13") (pin "1") (pinfunction "1_1") (pintype "passive"))
      (node (ref "R15") (pin "2") (pinfunction "2_2") (pintype "passive"))
      (node (ref "U3") (pin "7") (pinfunction "FB-_7") (pintype "input"))
    )
    (net (code "9") (name "/5PS_Dual_Out+") (class "Default")
      (node (ref "C18") (pin "2") (pinfunction "2_2") (pintype "passive"))
      (node (ref "R7") (pin "2") (pinfunction "2_2") (pintype "passive"))
      (node (ref "R8") (pin "1") (pinfunction "1_1") (pintype "passive"))
      (node (ref "R9") (pin "2") (pinfunction "2_2") (pintype "passive"))
      (node (ref "U3") (pin "11") (pinfunction "OUT+_11") (pintype "passive"))
    )
    (net (code "10") (name "/5PS_Dual_Out-") (class "Default")
      (node (ref "C22") (pin "1") (pinfunction "1_1") (pintype "passive"))
      (node (ref "LD3") (pin "2") (pinfunction "K_2") (pintype "passive"))
      (node (ref "R15") (pin "1") (pinfunction "1_1") (pintype "passive"))
      (node (ref "R16") (pin "2") (pinfunction "2_2") (pintype "passive"))
      (node (ref "U3") (pin "6") (pinfunction "OUT-_6") (pintype "passive"))
    )
    (net (code "11") (name "/5PS_Dual_Out_2-") (class "Default")
      (node (ref "R16") (pin "1") (pinfunction "1_1") (pintype "passive"))
      (node (ref "R5") (pin "1") (pinfunction "1_1") (pintype "passive"))
    )
    (net (code "12") (name "/5PS_Dual_Out_3+") (class "Default")
      (node (ref "R6") (pin "1") (pinfunction "1_1") (pintype "passive"))
      (node (ref "R7") (pin "1") (pinfunction "1_1") (pintype "passive"))
    )
    (net (code "13") (name "/5PS_Dual_Pgood") (class "Default")
      (node (ref "R12") (pin "2") (pinfunction "2_2") (pintype "passive"))
      (node (ref "U3") (pin "1") (pinfunction "PGOOD_1") (pintype "open_collector"))
    )
    (net (code "14") (name "/5PS_Dual_Vin") (class "Default")
      (node (ref "C20") (pin "2") (pinfunction "2_2") (pintype "passive"))
      (node (ref "R11") (pin "1") (pinfunction "1_1") (pintype "passive"))
      (node (ref "R12") (pin "1") (pinfunction "1_1") (pintype "passive"))
      (node (ref "U3") (pin "3") (pinfunction "VIN_3") (pintype "power_in"))
    )
    (net (code "15") (name "/5PowCtrl_MCU") (class "Default")
      (node (ref "D6") (pin "2") (pinfunction "A_2") (pintype "passive"))
      (node (ref "R20") (pin "1") (pinfunction "1_1") (pintype "passive"))
      (node (ref "U6") (pin "23") (pinfunction "IO15_23") (pintype "bidirectional"))
    )
    (net (code "16") (name "/5ToAMP") (class "Default")
      (node (ref "Q2") (pin "2") (pinfunction "S_2") (pintype "passive"))
      (node (ref "R24") (pin "1") (pinfunction "1_1") (pintype "passive"))
    )
    (net (code "17") (name "/12PS5_SW") (class "Default")
      (node (ref "C2") (pin "2") (pinfunction "2_2") (pintype "passive"))
      (node (ref "L2") (pin "1") (pinfunction "1_1") (pintype "passive"))
      (node (ref "U1") (pin "2") (pinfunction "SW_2") (pintype "bidirectional"))
    )
    (net (code "18") (name "/12PS5_Vfb") (class "Default")
      (node (ref "R2") (pin "1") (pinfunction "1_1") (pintype "passive"))
      (node (ref "R4") (pin "2") (pinfunction "2_2") (pintype "passive"))
      (node (ref "U1") (pin "4") (pinfunction "VFB_4") (pintype "bidirectional"))
    )
    (net (code "19") (name "/12PowCtrl_MCU") (class "Default")
      (node (ref "D5") (pin "2") (pinfunction "A_2") (pintype "passive"))
      (node (ref "R19") (pin "1") (pinfunction "1_1") (pintype "passive"))
      (node (ref "U6") (pin "13") (pinfunction "IO14_13") (pintype "bidirectional"))
    )
    (net (code "20") (name "/12ToAMP") (class "Default")
      (node (ref "Q1") (pin "2") (pinfunction "S_2") (pintype "passive"))
      (node (ref "R23") (pin "1") (pinfunction "1_1") (pintype "passive"))
    )
    (net (code "22") (name "/AMP_ACG1") (class "Default")
      (node (ref "C9") (pin "1") (pinfunction "1_1") (pintype "passive"))
      (node (ref "U2") (pin "30") (pinfunction "ACG1_30") (pintype "power_in"))
    )
    (net (code "23") (name "/AMP_ACG2") (class "Default")
      (node (ref "C10") (pin "1") (pinfunction "1_1") (pintype "passive"))
      (node (ref "U2") (pin "29") (pinfunction "ACG2_29") (pintype "power_in"))
    )
    (net (code "24") (name "/AMP_ACG3") (class "Default")
      (node (ref "C11") (pin "1") (pinfunction "1_1") (pintype "passive"))
      (node (ref "U2") (pin "16") (pinfunction "ACG3_16") (pintype "power_in"))
    )
    (net (code "25") (name "/AMP_ACG4") (class "Default")
      (node (ref "C12") (pin "1") (pinfunction "1_1") (pintype "passive"))
      (node (ref "U2") (pin "15") (pinfunction "ACG4_15") (pintype "power_in"))
    )
    (net (code "26") (name "/AMP_VGG1") (class "Default")
      (node (ref "C13") (pin "1") (pinfunction "1_1") (pintype "passive"))
      (node (ref "C14") (pin "1") (pinfunction "1_1") (pintype "passive"))
      (node (ref "C15") (pin "1") (pinfunction "1_1") (pintype "passive"))
      (node (ref "R5") (pin "2") (pinfunction "2_2") (pintype "passive"))
      (node (ref "U2") (pin "13") (pinfunction "VGG1_13") (pintype "power_in"))
    )
    (net (code "27") (name "/AMP_VGG2") (class "Default")
      (node (ref "C16") (pin "1") (pinfunction "1_1") (pintype "passive"))
      (node (ref "C17") (pin "1") (pinfunction "1_1") (pintype "passive"))
      (node (ref "R24") (pin "2") (pinfunction "2_2") (pintype "passive"))
      (node (ref "U2") (pin "2") (pinfunction "VGG2_2") (pintype "power_in"))
    )
    (net (code "28") (name "/ESP32_Bridge_RXD") (class "Default")
      (node (ref "R33") (pin "1") (pinfunction "1_1") (pintype "passive"))
      (node (ref "U7") (pin "25") (pinfunction "RXD_25") (pintype "input"))
    )
    (net (code "29") (name "/ESP32_Bridge_TXD") (class "Default")
      (node (ref "R32") (pin "1") (pinfunction "1_1") (pintype "passive"))
      (node (ref "U7") (pin "26") (pinfunction "TXD_26") (pintype "output"))
    )
    (net (code "30") (name "/ESP32_DTR") (class "Default")
      (node (ref "Q6") (pin "2") (pinfunction "E_2") (pintype "passive"))
      (node (ref "R34") (pin "2") (pinfunction "2_2") (pintype "passive"))
      (node (ref "U7") (pin "28") (pinfunction "~{DTR}_28") (pintype "output"))
    )
    (net (code "31") (name "/ESP32_EN") (class "Default")
      (node (ref "C28") (pin "1") (pinfunction "1_1") (pintype "passive"))
      (node (ref "Q5") (pin "3") (pinfunction "C_3") (pintype "passive"))
      (node (ref "R26") (pin "2") (pinfunction "2_2") (pintype "passive"))
      (node (ref "R30") (pin "1") (pinfunction "1_1") (pintype "passive"))
      (node (ref "U6") (pin "3") (pinfunction "EN_3") (pintype "input"))
    )
    (net (code "32") (name "/ESP32_IO0") (class "Default")
      (node (ref "Q6") (pin "3") (pinfunction "C_3") (pintype "passive"))
      (node (ref "R25") (pin "2") (pinfunction "2_2") (pintype "passive"))
      (node (ref "R29") (pin "1") (pinfunction "1_1") (pintype "passive"))
      (node (ref "U6") (pin "25") (pinfunction "IO0_25") (pintype "bidirectional"))
    )
    (net (code "33") (name "/ESP32_RTS") (class "Default")
      (node (ref "Q5") (pin "2") (pinfunction "E_2") (pintype "passive"))
      (node (ref "R36") (pin "1") (pinfunction "1_1") (pintype "passive"))
      (node (ref "U7") (pin "24") (pinfunction "~{RTS}_24") (pintype "output"))
    )
    (net (code "34") (name "/ESP32_RX0") (class "Default")
      (node (ref "R32") (pin "2") (pinfunction "2_2") (pintype "passive"))
      (node (ref "U6") (pin "34") (pinfunction "RXD0_34") (pintype "bidirectional"))
    )
    (net (code "35") (name "/ESP32_TX0") (class "Default")
      (node (ref "R33") (pin "2") (pinfunction "2_2") (pintype "passive"))
      (node (ref "U6") (pin "35") (pinfunction "TXD0_35") (pintype "bidirectional"))
    )
    (net (code "36") (name "/ESP32_USB_D_N") (class "Default")
      (node (ref "D2") (pin "A") (pinfunction "A_A") (pintype "passive"))
      (node (ref "J3") (pin "2") (pinfunction "D-_2") (pintype "passive"))
      (node (ref "U7") (pin "4") (pinfunction "D+_4") (pintype "bidirectional"))
    )
    (net (code "37") (name "/ESP32_USB_D_P") (class "Default")
      (node (ref "D1") (pin "A") (pinfunction "A_A") (pintype "passive"))
      (node (ref "J3") (pin "3") (pinfunction "D+_3") (pintype "passive"))
      (node (ref "U7") (pin "5") (pinfunction "D-_5") (pintype "bidirectional"))
    )
    (net (code "38") (name "/ESP32_Vbus") (class "Default")
      (node (ref "D3") (pin "A") (pinfunction "A_A") (pintype "passive"))
      (node (ref "J3") (pin "1") (pinfunction "VBUS_1") (pintype "passive"))
      (node (ref "U7") (pin "8") (pinfunction "VBUS_8") (pintype "input"))
    )
    (net (code "39") (name "/RF_AMP_OUT") (class "Default")
      (node (ref "C1") (pin "2") (pinfunction "2_2") (pintype "passive"))
      (node (ref "J1") (pin "1") (pinfunction "1_1") (pintype "passive"))
    )
    (net (code "40") (name "/VcoRfOut") (class "Default")
      (node (ref "C3") (pin "1") (pinfunction "1_1") (pintype "passive"))
      (node (ref "U4") (pin "8") (pinfunction "RFOUT_8") (pintype "output"))
    )
    (net (code "41") (name "12PS5_Out") (class "Default")
      (node (ref "C27") (pin "2") (pinfunction "2_2") (pintype "passive"))
      (node (ref "Q2") (pin "3") (pinfunction "D_3") (pintype "passive"))
      (node (ref "R1") (pin "1") (pinfunction "1_1") (pintype "passive"))
      (node (ref "R11") (pin "2") (pinfunction "2_2") (pintype "passive"))
      (node (ref "R18") (pin "2") (pinfunction "2_2") (pintype "passive"))
      (node (ref "R27") (pin "2") (pinfunction "2_2") (pintype "passive"))
      (node (ref "R3") (pin "1") (pinfunction "1_1") (pintype "passive"))
      (node (ref "U5") (pin "3") (pinfunction "IN_3") (pintype "power_in"))
    )
    (net (code "42") (name "ESP32_3V3") (class "Default")
      (node (ref "C26") (pin "2") (pinfunction "2_2") (pintype "passive"))
      (node (ref "C30") (pin "2") (pinfunction "2_2") (pintype "passive"))
      (node (ref "C31") (pin "2") (pinfunction "2_2") (pintype "passive"))
      (node (ref "R25") (pin "1") (pinfunction "1_1") (pintype "passive"))
      (node (ref "R26") (pin "1") (pinfunction "1_1") (pintype "passive"))
      (node (ref "R28") (pin "2") (pinfunction "2_2") (pintype "passive"))
      (node (ref "R35") (pin "1") (pinfunction "1_1") (pintype "passive"))
      (node (ref "U5") (pin "2") (pinfunction "OUT_2") (pintype "power_in"))
      (node (ref "U6") (pin "2") (pinfunction "3V3_2") (pintype "power_in"))
      (node (ref "U7") (pin "6") (pinfunction "VDD_6") (pintype "power_in"))
      (node (ref "U7") (pin "7") (pinfunction "REGIN_7") (pintype "power_in"))
    )
    (net (code "43") (name "GND") (class "Default")
      (node (ref "C10") (pin "2") (pinfunction "2_2") (pintype "passive"))
      (node (ref "C11") (pin "2") (pinfunction "2_2") (pintype "passive"))
      (node (ref "C12") (pin "2") (pinfunction "2_2") (pintype "passive"))
      (node (ref "C13") (pin "2") (pinfunction "2_2") (pintype "passive"))
      (node (ref "C14") (pin "2") (pinfunction "2_2") (pintype "passive"))
      (node (ref "C15") (pin "2") (pinfunction "2_2") (pintype "passive"))
      (node (ref "C16") (pin "2") (pinfunction "2_2") (pintype "passive"))
      (node (ref "C17") (pin "2") (pinfunction "2_2") (pintype "passive"))
      (node (ref "C18") (pin "1") (pinfunction "1_1") (pintype "passive"))
      (node (ref "C19") (pin "2") (pinfunction "2_2") (pintype "passive"))
      (node (ref "C20") (pin "1") (pinfunction "1_1") (pintype "passive"))
      (node (ref "C21") (pin "1") (pinfunction "1_1") (pintype "passive"))
      (node (ref "C22") (pin "2") (pinfunction "2_2") (pintype "passive"))
      (node (ref "C24") (pin "2") (pinfunction "2_2") (pintype "passive"))
      (node (ref "C25") (pin "2") (pinfunction "2_2") (pintype "passive"))
      (node (ref "C26") (pin "1") (pinfunction "1_1") (pintype "passive"))
      (node (ref "C27") (pin "1") (pinfunction "1_1") (pintype "passive"))
      (node (ref "C28") (pin "2") (pinfunction "2_2") (pintype "passive"))
      (node (ref "C29") (pin "1") (pinfunction "1_1") (pintype "passive"))
      (node (ref "C30") (pin "1") (pinfunction "1_1") (pintype "passive"))
      (node (ref "C31") (pin "1") (pinfunction "1_1") (pintype "passive"))
      (node (ref "C4") (pin "2") (pinfunction "2_2") (pintype "passive"))
      (node (ref "C5") (pin "2") (pinfunction "2_2") (pintype "passive"))
      (node (ref "C6") (pin "2") (pinfunction "2_2") (pintype "passive"))
      (node (ref "C7") (pin "2") (pinfunction "2_2") (pintype "passive"))
      (node (ref "C8") (pin "2") (pinfunction "2_2") (pintype "passive"))
      (node (ref "C9") (pin "2") (pinfunction "2_2") (pintype "passive"))
      (node (ref "D1") (pin "C") (pinfunction "C_C") (pintype "passive"))
      (node (ref "D2") (pin "C") (pinfunction "C_C") (pintype "passive"))
      (node (ref "D3") (pin "C") (pinfunction "C_C") (pintype "passive"))
      (node (ref "J1") (pin "2") (pinfunction "MNT_1_2") (pintype "passive"))
      (node (ref "J1") (pin "3") (pinfunction "MNT_2_3") (pintype "passive"))
      (node (ref "J1") (pin "4") (pinfunction "MNT_3_4") (pintype "passive"))
      (node (ref "J1") (pin "5") (pinfunction "MNT_4_5") (pintype "passive"))
      (node (ref "J2") (pin "2") (pinfunction "MNT_1_2") (pintype "passive"))
      (node (ref "J2") (pin "3") (pinfunction "MNT_2_3") (pintype "passive"))
      (node (ref "J2") (pin "4") (pinfunction "MNT_3_4") (pintype "passive"))
      (node (ref "J2") (pin "5") (pinfunction "MNT_4_5") (pintype "passive"))
      (node (ref "J3") (pin "5") (pinfunction "GND_5") (pintype "passive"))
      (node (ref "LD1") (pin "2") (pinfunction "K_2") (pintype "passive"))
      (node (ref "LD2") (pin "2") (pinfunction "K_2") (pintype "passive"))
      (node (ref "LD4") (pin "2") (pinfunction "K_2") (pintype "passive"))
      (node (ref "R10") (pin "1") (pinfunction "1_1") (pintype "passive"))
      (node (ref "R13") (pin "2") (pinfunction "2_2") (pintype "passive"))
      (node (ref "R14") (pin "1") (pinfunction "1_1") (pintype "passive"))
      (node (ref "R21") (pin "1") (pinfunction "1_1") (pintype "passive"))
      (node (ref "R22") (pin "1") (pinfunction "1_1") (pintype "passive"))
      (node (ref "R31") (pin "1") (pinfunction "1_1") (pintype "passive"))
      (node (ref "R37") (pin "2") (pinfunction "2_2") (pintype "passive"))
      (node (ref "R38") (pin "2") (pinfunction "2_2") (pintype "passive"))
      (node (ref "R39") (pin "2") (pinfunction "2_2") (pintype "passive"))
      (node (ref "R4") (pin "1") (pinfunction "1_1") (pintype "passive"))
      (node (ref "R40") (pin "2") (pinfunction "2_2") (pintype "passive"))
      (node (ref "SW1") (pin "4") (pinfunction "4_4") (pintype "passive"))
      (node (ref "SW2") (pin "4") (pinfunction "4_4") (pintype "passive"))
      (node (ref "U1") (pin "1") (pinfunction "GND_1") (pintype "power_in"))
      (node (ref "U2") (pin "12") (pinfunction "GND_12") (pintype "power_in"))
      (node (ref "U2") (pin "22") (pinfunction "GND_22") (pintype "power_in"))
      (node (ref "U2") (pin "33") (pinfunction "EP_33") (pintype "power_in"))
      (node (ref "U2") (pin "4") (pinfunction "GND_4") (pintype "power_in"))
      (node (ref "U3") (pin "13") (pinfunction "Thermal_Pad_13") (pintype "passive"))
      (node (ref "U3") (pin "4") (pinfunction "GND_4") (pintype "power_in"))
      (node (ref "U4") (pin "4") (pinfunction "GND_4") (pintype "power_in"))
      (node (ref "U4") (pin "5") (pinfunction "GND_5") (pintype "power_in"))
      (node (ref "U4") (pin "9") (pinfunction "GND_9") (pintype "power_in"))
      (node (ref "U6") (pin "1") (pinfunction "GND_1") (pintype "power_in"))
      (node (ref "U6") (pin "15") (pinfunction "GND_15") (pintype "power_in"))
      (node (ref "U6") (pin "38") (pinfunction "GND_38") (pintype "power_in"))
      (node (ref "U6") (pin "39_1") (pinfunction "GND_39_1") (pintype "power_in"))
      (node (ref "U6") (pin "39_2") (pinfunction "GND_39_2") (pintype "power_in"))
      (node (ref "U6") (pin "39_3") (pinfunction "GND_39_3") (pintype "power_in"))
      (node (ref "U6") (pin "39_4") (pinfunction "GND_39_4") (pintype "power_in"))
      (node (ref "U6") (pin "39_5") (pinfunction "GND_39_5") (pintype "power_in"))
      (node (ref "U6") (pin "39_6") (pinfunction "GND_39_6") (pintype "power_in"))
      (node (ref "U6") (pin "39_7") (pinfunction "GND_39_7") (pintype "power_in"))
      (node (ref "U6") (pin "39_8") (pinfunction "GND_39_8") (pintype "power_in"))
      (node (ref "U6") (pin "39_9") (pinfunction "GND_39_9") (pintype "power_in"))
      (node (ref "U7") (pin "29") (pinfunction "GND_29") (pintype "power_in"))
      (node (ref "U7") (pin "3") (pinfunction "GND_3") (pintype "power_in"))
    )
    (net (code "44") (name "Net-(C7-Pad1)") (class "Default")
      (node (ref "C7") (pin "1") (pinfunction "1_1") (pintype "passive"))
      (node (ref "C8") (pin "1") (pinfunction "1_1") (pintype "passive"))
      (node (ref "L2") (pin "2") (pinfunction "2_2") (pintype "passive"))
      (node (ref "R1") (pin "2") (pinfunction "2_2") (pintype "passive"))
      (node (ref "R2") (pin "2") (pinfunction "2_2") (pintype "passive"))
    )
    (net (code "45") (name "Net-(C24-Pad1)") (class "Default")
      (node (ref "C24") (pin "1") (pinfunction "1_1") (pintype "passive"))
      (node (ref "R29") (pin "2") (pinfunction "2_2") (pintype "passive"))
      (node (ref "SW1") (pin "2") (pinfunction "2_2") (pintype "passive"))
    )
    (net (code "46") (name "Net-(C25-Pad1)") (class "Default")
      (node (ref "C25") (pin "1") (pinfunction "1_1") (pintype "passive"))
      (node (ref "R30") (pin "2") (pinfunction "2_2") (pintype "passive"))
      (node (ref "SW2") (pin "2") (pinfunction "2_2") (pintype "passive"))
    )
    (net (code "47") (name "Net-(D4-C)") (class "Default")
      (node (ref "D4") (pin "1") (pinfunction "C_1") (pintype "passive"))
      (node (ref "R37") (pin "1") (pinfunction "1_1") (pintype "passive"))
    )
    (net (code "48") (name "Net-(D5-C)") (class "Default")
      (node (ref "D5") (pin "1") (pinfunction "C_1") (pintype "passive"))
      (node (ref "R38") (pin "1") (pinfunction "1_1") (pintype "passive"))
    )
    (net (code "49") (name "Net-(D6-C)") (class "Default")
      (node (ref "D6") (pin "1") (pinfunction "C_1") (pintype "passive"))
      (node (ref "R39") (pin "1") (pinfunction "1_1") (pintype "passive"))
    )
    (net (code "50") (name "Net-(D7-C)") (class "Default")
      (node (ref "D7") (pin "1") (pinfunction "C_1") (pintype "passive"))
      (node (ref "R40") (pin "1") (pinfunction "1_1") (pintype "passive"))
    )
    (net (code "51") (name "Net-(LD1-A)") (class "Default")
      (node (ref "LD1") (pin "1") (pinfunction "A_1") (pintype "passive"))
      (node (ref "R3") (pin "2") (pinfunction "2_2") (pintype "passive"))
    )
    (net (code "52") (name "Net-(LD2-A)") (class "Default")
      (node (ref "LD2") (pin "1") (pinfunction "A_1") (pintype "passive"))
      (node (ref "R8") (pin "2") (pinfunction "2_2") (pintype "passive"))
    )
    (net (code "53") (name "Net-(LD3-A)") (class "Default")
      (node (ref "LD3") (pin "1") (pinfunction "A_1") (pintype "passive"))
      (node (ref "R14") (pin "2") (pinfunction "2_2") (pintype "passive"))
    )
    (net (code "54") (name "Net-(LD4-A)") (class "Default")
      (node (ref "LD4") (pin "1") (pinfunction "A_1") (pintype "passive"))
      (node (ref "R27") (pin "1") (pinfunction "1_1") (pintype "passive"))
    )
    (net (code "55") (name "Net-(Q1-G)") (class "Default")
      (node (ref "Q1") (pin "1") (pinfunction "G_1") (pintype "passive"))
      (node (ref "Q3") (pin "3") (pinfunction "C_3") (pintype "passive"))
      (node (ref "R17") (pin "1") (pinfunction "1_1") (pintype "passive"))
    )
    (net (code "56") (name "Net-(Q2-G)") (class "Default")
      (node (ref "Q2") (pin "1") (pinfunction "G_1") (pintype "passive"))
      (node (ref "Q4") (pin "3") (pinfunction "C_3") (pintype "passive"))
      (node (ref "R18") (pin "1") (pinfunction "1_1") (pintype "passive"))
    )
    (net (code "57") (name "Net-(Q3-B)") (class "Default")
      (node (ref "Q3") (pin "1") (pinfunction "B_1") (pintype "passive"))
      (node (ref "R19") (pin "2") (pinfunction "2_2") (pintype "passive"))
    )
    (net (code "58") (name "Net-(Q3-E)") (class "Default")
      (node (ref "Q3") (pin "2") (pinfunction "E_2") (pintype "passive"))
      (node (ref "R21") (pin "2") (pinfunction "2_2") (pintype "passive"))
    )
    (net (code "59") (name "Net-(Q4-B)") (class "Default")
      (node (ref "Q4") (pin "1") (pinfunction "B_1") (pintype "passive"))
      (node (ref "R20") (pin "2") (pinfunction "2_2") (pintype "passive"))
    )
    (net (code "60") (name "Net-(Q4-E)") (class "Default")
      (node (ref "Q4") (pin "2") (pinfunction "E_2") (pintype "passive"))
      (node (ref "R22") (pin "2") (pinfunction "2_2") (pintype "passive"))
    )
    (net (code "61") (name "Net-(Q5-B)") (class "Default")
      (node (ref "Q5") (pin "1") (pinfunction "B_1") (pintype "passive"))
      (node (ref "R34") (pin "1") (pinfunction "1_1") (pintype "passive"))
    )
    (net (code "62") (name "Net-(Q6-B)") (class "Default")
      (node (ref "Q6") (pin "1") (pinfunction "B_1") (pintype "passive"))
      (node (ref "R36") (pin "2") (pinfunction "2_2") (pintype "passive"))
    )
    (net (code "63") (name "Net-(U1-VBST)") (class "Default")
      (node (ref "C2") (pin "1") (pinfunction "1_1") (pintype "passive"))
      (node (ref "U1") (pin "6") (pinfunction "VBST_6") (pintype "bidirectional"))
    )
    (net (code "64") (name "Net-(U2-RFIN)") (class "Default")
      (node (ref "C3") (pin "2") (pinfunction "2_2") (pintype "passive"))
      (node (ref "U2") (pin "5") (pinfunction "RFIN_5") (pintype "passive"))
    )
    (net (code "65") (name "Net-(U2-RFOUT{slash}VDD)") (class "Default")
      (node (ref "C1") (pin "1") (pinfunction "1_1") (pintype "passive"))
      (node (ref "L1") (pin "2") (pinfunction "2_2") (pintype "passive"))
      (node (ref "U2") (pin "21") (pinfunction "RFOUT/VDD_21") (pintype "output"))
    )
    (net (code "66") (name "Net-(U5-ADJ{slash}GND)") (class "Default")
      (node (ref "C29") (pin "2") (pinfunction "2_2") (pintype "passive"))
      (node (ref "R28") (pin "1") (pinfunction "1_1") (pintype "passive"))
      (node (ref "R31") (pin "2") (pinfunction "2_2") (pintype "passive"))
      (node (ref "U5") (pin "1") (pinfunction "ADJ/GND_1") (pintype "passive"))
    )
    (net (code "67") (name "Net-(U7A-~{RST})") (class "Default")
      (node (ref "R35") (pin "2") (pinfunction "2_2") (pintype "passive"))
      (node (ref "U7") (pin "9") (pinfunction "~{RST}_9") (pintype "bidirectional"))
    )
    (net (code "68") (name "RF_AMP_VDD_12V") (class "Default")
      (node (ref "L1") (pin "1") (pinfunction "1_1") (pintype "passive"))
      (node (ref "R23") (pin "2") (pinfunction "2_2") (pintype "passive"))
    )
    (net (code "69") (name "VcoVcc3V") (class "Default")
      (node (ref "C19") (pin "1") (pinfunction "1_1") (pintype "passive"))
      (node (ref "R6") (pin "2") (pinfunction "2_2") (pintype "passive"))
      (node (ref "U4") (pin "1") (pinfunction "VCC_1") (pintype "power_in"))
      (node (ref "U4") (pin "3") (pinfunction "VTUNE_3") (pintype "passive"))
    )
    (net (code "70") (name "unconnected-(J3-ID-Pad4)") (class "Default")
      (node (ref "J3") (pin "4") (pinfunction "ID_4") (pintype "passive+no_connect"))
    )
    (net (code "71") (name "unconnected-(J3-SHLD1-Pad6)") (class "Default")
      (node (ref "J3") (pin "6") (pinfunction "SHLD1_6") (pintype "passive+no_connect"))
    )
    (net (code "72") (name "unconnected-(J3-SHLD2-Pad7)") (class "Default")
      (node (ref "J3") (pin "7") (pinfunction "SHLD2_7") (pintype "passive+no_connect"))
    )
    (net (code "73") (name "unconnected-(J3-SHLD3-Pad8)") (class "Default")
      (node (ref "J3") (pin "8") (pinfunction "SHLD3_8") (pintype "passive+no_connect"))
    )
    (net (code "74") (name "unconnected-(J3-SHLD4-Pad9)") (class "Default")
      (node (ref "J3") (pin "9") (pinfunction "SHLD4_9") (pintype "passive+no_connect"))
    )
    (net (code "75") (name "unconnected-(J3-SHLD5-Pad10)") (class "Default")
      (node (ref "J3") (pin "10") (pinfunction "SHLD5_10") (pintype "passive+no_connect"))
    )
    (net (code "76") (name "unconnected-(J3-SHLD6-Pad11)") (class "Default")
      (node (ref "J3") (pin "11") (pinfunction "SHLD6_11") (pintype "passive+no_connect"))
    )
    (net (code "77") (name "unconnected-(SW1-Pad1)") (class "Default")
      (node (ref "SW1") (pin "1") (pinfunction "1_1") (pintype "passive+no_connect"))
    )
    (net (code "78") (name "unconnected-(SW1-Pad3)") (class "Default")
      (node (ref "SW1") (pin "3") (pinfunction "3_3") (pintype "passive+no_connect"))
    )
    (net (code "79") (name "unconnected-(SW2-Pad1)") (class "Default")
      (node (ref "SW2") (pin "1") (pinfunction "1_1") (pintype "passive+no_connect"))
    )
    (net (code "80") (name "unconnected-(SW2-Pad3)") (class "Default")
      (node (ref "SW2") (pin "3") (pinfunction "3_3") (pintype "passive+no_connect"))
    )
    (net (code "81") (name "unconnected-(U2-NC-Pad1)") (class "Default")
      (node (ref "U2") (pin "1") (pinfunction "NC_1") (pintype "passive+no_connect"))
    )
    (net (code "82") (name "unconnected-(U2-NC-Pad3)") (class "Default")
      (node (ref "U2") (pin "3") (pinfunction "NC_3") (pintype "passive+no_connect"))
    )
    (net (code "83") (name "unconnected-(U2-NC-Pad6)") (class "Default")
      (node (ref "U2") (pin "6") (pinfunction "NC_6") (pintype "passive+no_connect"))
    )
    (net (code "84") (name "unconnected-(U2-NC-Pad7)") (class "Default")
      (node (ref "U2") (pin "7") (pinfunction "NC_7") (pintype "passive+no_connect"))
    )
    (net (code "85") (name "unconnected-(U2-NC-Pad8)") (class "Default")
      (node (ref "U2") (pin "8") (pinfunction "NC_8") (pintype "passive+no_connect"))
    )
    (net (code "86") (name "unconnected-(U2-NC-Pad9)") (class "Default")
      (node (ref "U2") (pin "9") (pinfunction "NC_9") (pintype "passive+no_connect"))
    )
    (net (code "87") (name "unconnected-(U2-NC-Pad10)") (class "Default")
      (node (ref "U2") (pin "10") (pinfunction "NC_10") (pintype "passive+no_connect"))
    )
    (net (code "88") (name "unconnected-(U2-NC-Pad11)") (class "Default")
      (node (ref "U2") (pin "11") (pinfunction "NC_11") (pintype "passive+no_connect"))
    )
    (net (code "89") (name "unconnected-(U2-NC-Pad14)") (class "Default")
      (node (ref "U2") (pin "14") (pinfunction "NC_14") (pintype "passive+no_connect"))
    )
    (net (code "90") (name "unconnected-(U2-NC-Pad17)") (class "Default")
      (node (ref "U2") (pin "17") (pinfunction "NC_17") (pintype "passive+no_connect"))
    )
    (net (code "91") (name "unconnected-(U2-NC-Pad18)") (class "Default")
      (node (ref "U2") (pin "18") (pinfunction "NC_18") (pintype "passive+no_connect"))
    )
    (net (code "92") (name "unconnected-(U2-NC-Pad19)") (class "Default")
      (node (ref "U2") (pin "19") (pinfunction "NC_19") (pintype "passive+no_connect"))
    )
    (net (code "93") (name "unconnected-(U2-NC-Pad20)") (class "Default")
      (node (ref "U2") (pin "20") (pinfunction "NC_20") (pintype "passive+no_connect"))
    )
    (net (code "94") (name "unconnected-(U2-NC-Pad23)") (class "Default")
      (node (ref "U2") (pin "23") (pinfunction "NC_23") (pintype "passive+no_connect"))
    )
    (net (code "95") (name "unconnected-(U2-NC-Pad24)") (class "Default")
      (node (ref "U2") (pin "24") (pinfunction "NC_24") (pintype "passive+no_connect"))
    )
    (net (code "96") (name "unconnected-(U2-NC-Pad25)") (class "Default")
      (node (ref "U2") (pin "25") (pinfunction "NC_25") (pintype "passive+no_connect"))
    )
    (net (code "97") (name "unconnected-(U2-NC-Pad26)") (class "Default")
      (node (ref "U2") (pin "26") (pinfunction "NC_26") (pintype "passive+no_connect"))
    )
    (net (code "98") (name "unconnected-(U2-NC-Pad27)") (class "Default")
      (node (ref "U2") (pin "27") (pinfunction "NC_27") (pintype "passive+no_connect"))
    )
    (net (code "99") (name "unconnected-(U2-NC-Pad28)") (class "Default")
      (node (ref "U2") (pin "28") (pinfunction "NC_28") (pintype "passive+no_connect"))
    )
    (net (code "100") (name "unconnected-(U2-NC-Pad31)") (class "Default")
      (node (ref "U2") (pin "31") (pinfunction "NC_31") (pintype "passive+no_connect"))
    )
    (net (code "101") (name "unconnected-(U2-NC-Pad32)") (class "Default")
      (node (ref "U2") (pin "32") (pinfunction "NC_32") (pintype "passive+no_connect"))
    )
    (net (code "102") (name "unconnected-(U4-NC-Pad2)") (class "Default")
      (node (ref "U4") (pin "2") (pinfunction "NC_2") (pintype "passive+no_connect"))
    )
    (net (code "103") (name "unconnected-(U4-NC-Pad6)") (class "Default")
      (node (ref "U4") (pin "6") (pinfunction "NC_6") (pintype "passive+no_connect"))
    )
    (net (code "104") (name "unconnected-(U4-NC-Pad7)") (class "Default")
      (node (ref "U4") (pin "7") (pinfunction "NC_7") (pintype "passive+no_connect"))
    )
    (net (code "105") (name "unconnected-(U5-TAB-Pad4)") (class "Default")
      (node (ref "U5") (pin "4") (pinfunction "TAB_4") (pintype "passive+no_connect"))
    )
    (net (code "106") (name "unconnected-(U6-IO2-Pad24)") (class "Default")
      (node (ref "U6") (pin "24") (pinfunction "IO2_24") (pintype "bidirectional+no_connect"))
    )
    (net (code "107") (name "unconnected-(U6-IO4-Pad26)") (class "Default")
      (node (ref "U6") (pin "26") (pinfunction "IO4_26") (pintype "bidirectional+no_connect"))
    )
    (net (code "108") (name "unconnected-(U6-IO5-Pad29)") (class "Default")
      (node (ref "U6") (pin "29") (pinfunction "IO5_29") (pintype "bidirectional+no_connect"))
    )
    (net (code "109") (name "unconnected-(U6-IO12-Pad14)") (class "Default")
      (node (ref "U6") (pin "14") (pinfunction "IO12_14") (pintype "bidirectional+no_connect"))
    )
    (net (code "110") (name "unconnected-(U6-IO17-Pad28)") (class "Default")
      (node (ref "U6") (pin "28") (pinfunction "IO17_28") (pintype "bidirectional+no_connect"))
    )
    (net (code "111") (name "unconnected-(U6-IO18-Pad30)") (class "Default")
      (node (ref "U6") (pin "30") (pinfunction "IO18_30") (pintype "bidirectional+no_connect"))
    )
    (net (code "112") (name "unconnected-(U6-IO19-Pad31)") (class "Default")
      (node (ref "U6") (pin "31") (pinfunction "IO19_31") (pintype "bidirectional+no_connect"))
    )
    (net (code "113") (name "unconnected-(U6-IO21-Pad33)") (class "Default")
      (node (ref "U6") (pin "33") (pinfunction "IO21_33") (pintype "bidirectional"))
    )
    (net (code "114") (name "unconnected-(U6-IO22-Pad36)") (class "Default")
      (node (ref "U6") (pin "36") (pinfunction "IO22_36") (pintype "bidirectional+no_connect"))
    )
    (net (code "115") (name "unconnected-(U6-IO23-Pad37)") (class "Default")
      (node (ref "U6") (pin "37") (pinfunction "IO23_37") (pintype "bidirectional+no_connect"))
    )
    (net (code "116") (name "unconnected-(U6-IO25-Pad10)") (class "Default")
      (node (ref "U6") (pin "10") (pinfunction "IO25_10") (pintype "bidirectional+no_connect"))
    )
    (net (code "117") (name "unconnected-(U6-IO26-Pad11)") (class "Default")
      (node (ref "U6") (pin "11") (pinfunction "IO26_11") (pintype "bidirectional+no_connect"))
    )
    (net (code "118") (name "unconnected-(U6-IO27-Pad12)") (class "Default")
      (node (ref "U6") (pin "12") (pinfunction "IO27_12") (pintype "bidirectional+no_connect"))
    )
    (net (code "119") (name "unconnected-(U6-IO32-Pad8)") (class "Default")
      (node (ref "U6") (pin "8") (pinfunction "IO32_8") (pintype "bidirectional+no_connect"))
    )
    (net (code "120") (name "unconnected-(U6-IO33-Pad9)") (class "Default")
      (node (ref "U6") (pin "9") (pinfunction "IO33_9") (pintype "bidirectional+no_connect"))
    )
    (net (code "121") (name "unconnected-(U6-IO34-Pad6)") (class "Default")
      (node (ref "U6") (pin "6") (pinfunction "IO34_6") (pintype "input+no_connect"))
    )
    (net (code "122") (name "unconnected-(U6-IO35-Pad7)") (class "Default")
      (node (ref "U6") (pin "7") (pinfunction "IO35_7") (pintype "input+no_connect"))
    )
    (net (code "123") (name "unconnected-(U6-NC-Pad17)") (class "Default")
      (node (ref "U6") (pin "17") (pinfunction "NC_17") (pintype "passive+no_connect"))
    )
    (net (code "124") (name "unconnected-(U6-NC-Pad18)") (class "Default")
      (node (ref "U6") (pin "18") (pinfunction "NC_18") (pintype "passive+no_connect"))
    )
    (net (code "125") (name "unconnected-(U6-NC-Pad19)") (class "Default")
      (node (ref "U6") (pin "19") (pinfunction "NC_19") (pintype "passive+no_connect"))
    )
    (net (code "126") (name "unconnected-(U6-NC-Pad20)") (class "Default")
      (node (ref "U6") (pin "20") (pinfunction "NC_20") (pintype "passive+no_connect"))
    )
    (net (code "127") (name "unconnected-(U6-NC-Pad21)") (class "Default")
      (node (ref "U6") (pin "21") (pinfunction "NC_21") (pintype "passive+no_connect"))
    )
    (net (code "128") (name "unconnected-(U6-NC-Pad22)") (class "Default")
      (node (ref "U6") (pin "22") (pinfunction "NC_22") (pintype "passive+no_connect"))
    )
    (net (code "129") (name "unconnected-(U6-NC1-Pad32)") (class "Default")
      (node (ref "U6") (pin "32") (pinfunction "NC1_32") (pintype "passive+no_connect"))
    )
    (net (code "130") (name "unconnected-(U6-SENSOR_VN-Pad5)") (class "Default")
      (node (ref "U6") (pin "5") (pinfunction "SENSOR_VN_5") (pintype "input+no_connect"))
    )
    (net (code "131") (name "unconnected-(U6-SENSOR_VP-Pad4)") (class "Default")
      (node (ref "U6") (pin "4") (pinfunction "SENSOR_VP_4") (pintype "input+no_connect"))
    )
    (net (code "132") (name "unconnected-(U7A-SUSPEND-Pad12)") (class "Default")
      (node (ref "U7") (pin "12") (pinfunction "SUSPEND_12") (pintype "output+no_connect"))
    )
    (net (code "133") (name "unconnected-(U7A-~{CTS}-Pad23)") (class "Default")
      (node (ref "U7") (pin "23") (pinfunction "~{CTS}_23") (pintype "input+no_connect"))
    )
    (net (code "134") (name "unconnected-(U7A-~{DCD}-Pad1)") (class "Default")
      (node (ref "U7") (pin "1") (pinfunction "~{DCD}_1") (pintype "input+no_connect"))
    )
    (net (code "135") (name "unconnected-(U7A-~{DSR}-Pad27)") (class "Default")
      (node (ref "U7") (pin "27") (pinfunction "~{DSR}_27") (pintype "input+no_connect"))
    )
    (net (code "136") (name "unconnected-(U7A-~{RI}-Pad2)") (class "Default")
      (node (ref "U7") (pin "2") (pinfunction "~{RI}_2") (pintype "input+no_connect"))
    )
    (net (code "137") (name "unconnected-(U7A-~{SUSPEND}-Pad11)") (class "Default")
      (node (ref "U7") (pin "11") (pinfunction "~{SUSPEND}_11") (pintype "output+no_connect"))
    )
    (net (code "138") (name "unconnected-(U7B-NC-Pad10)") (class "Default")
      (node (ref "U7") (pin "10") (pinfunction "NC_10") (pintype "passive+no_connect"))
    )
    (net (code "139") (name "unconnected-(U7B-NC-Pad13)") (class "Default")
      (node (ref "U7") (pin "13") (pinfunction "NC_13") (pintype "passive+no_connect"))
    )
    (net (code "140") (name "unconnected-(U7B-NC-Pad14)") (class "Default")
      (node (ref "U7") (pin "14") (pinfunction "NC_14") (pintype "passive+no_connect"))
    )
    (net (code "141") (name "unconnected-(U7B-NC-Pad15)") (class "Default")
      (node (ref "U7") (pin "15") (pinfunction "NC_15") (pintype "passive+no_connect"))
    )
    (net (code "142") (name "unconnected-(U7B-NC-Pad16)") (class "Default")
      (node (ref "U7") (pin "16") (pinfunction "NC_16") (pintype "passive+no_connect"))
    )
    (net (code "143") (name "unconnected-(U7B-NC-Pad17)") (class "Default")
      (node (ref "U7") (pin "17") (pinfunction "NC_17") (pintype "passive+no_connect"))
    )
    (net (code "144") (name "unconnected-(U7B-NC-Pad18)") (class "Default")
      (node (ref "U7") (pin "18") (pinfunction "NC_18") (pintype "passive+no_connect"))
    )
    (net (code "145") (name "unconnected-(U7B-NC-Pad19)") (class "Default")
      (node (ref "U7") (pin "19") (pinfunction "NC_19") (pintype "passive+no_connect"))
    )
    (net (code "146") (name "unconnected-(U7B-NC-Pad20)") (class "Default")
      (node (ref "U7") (pin "20") (pinfunction "NC_20") (pintype "passive+no_connect"))
    )
    (net (code "147") (name "unconnected-(U7B-NC-Pad21)") (class "Default")
      (node (ref "U7") (pin "21") (pinfunction "NC_21") (pintype "passive+no_connect"))
    )
    (net (code "148") (name "unconnected-(U7B-NC-Pad22)") (class "Default")
      (node (ref "U7") (pin "22") (pinfunction "NC_22") (pintype "passive+no_connect"))
    )
  )
)
